# placa_nano.net
KiCad netlist of a schematic drawn in EAGLE
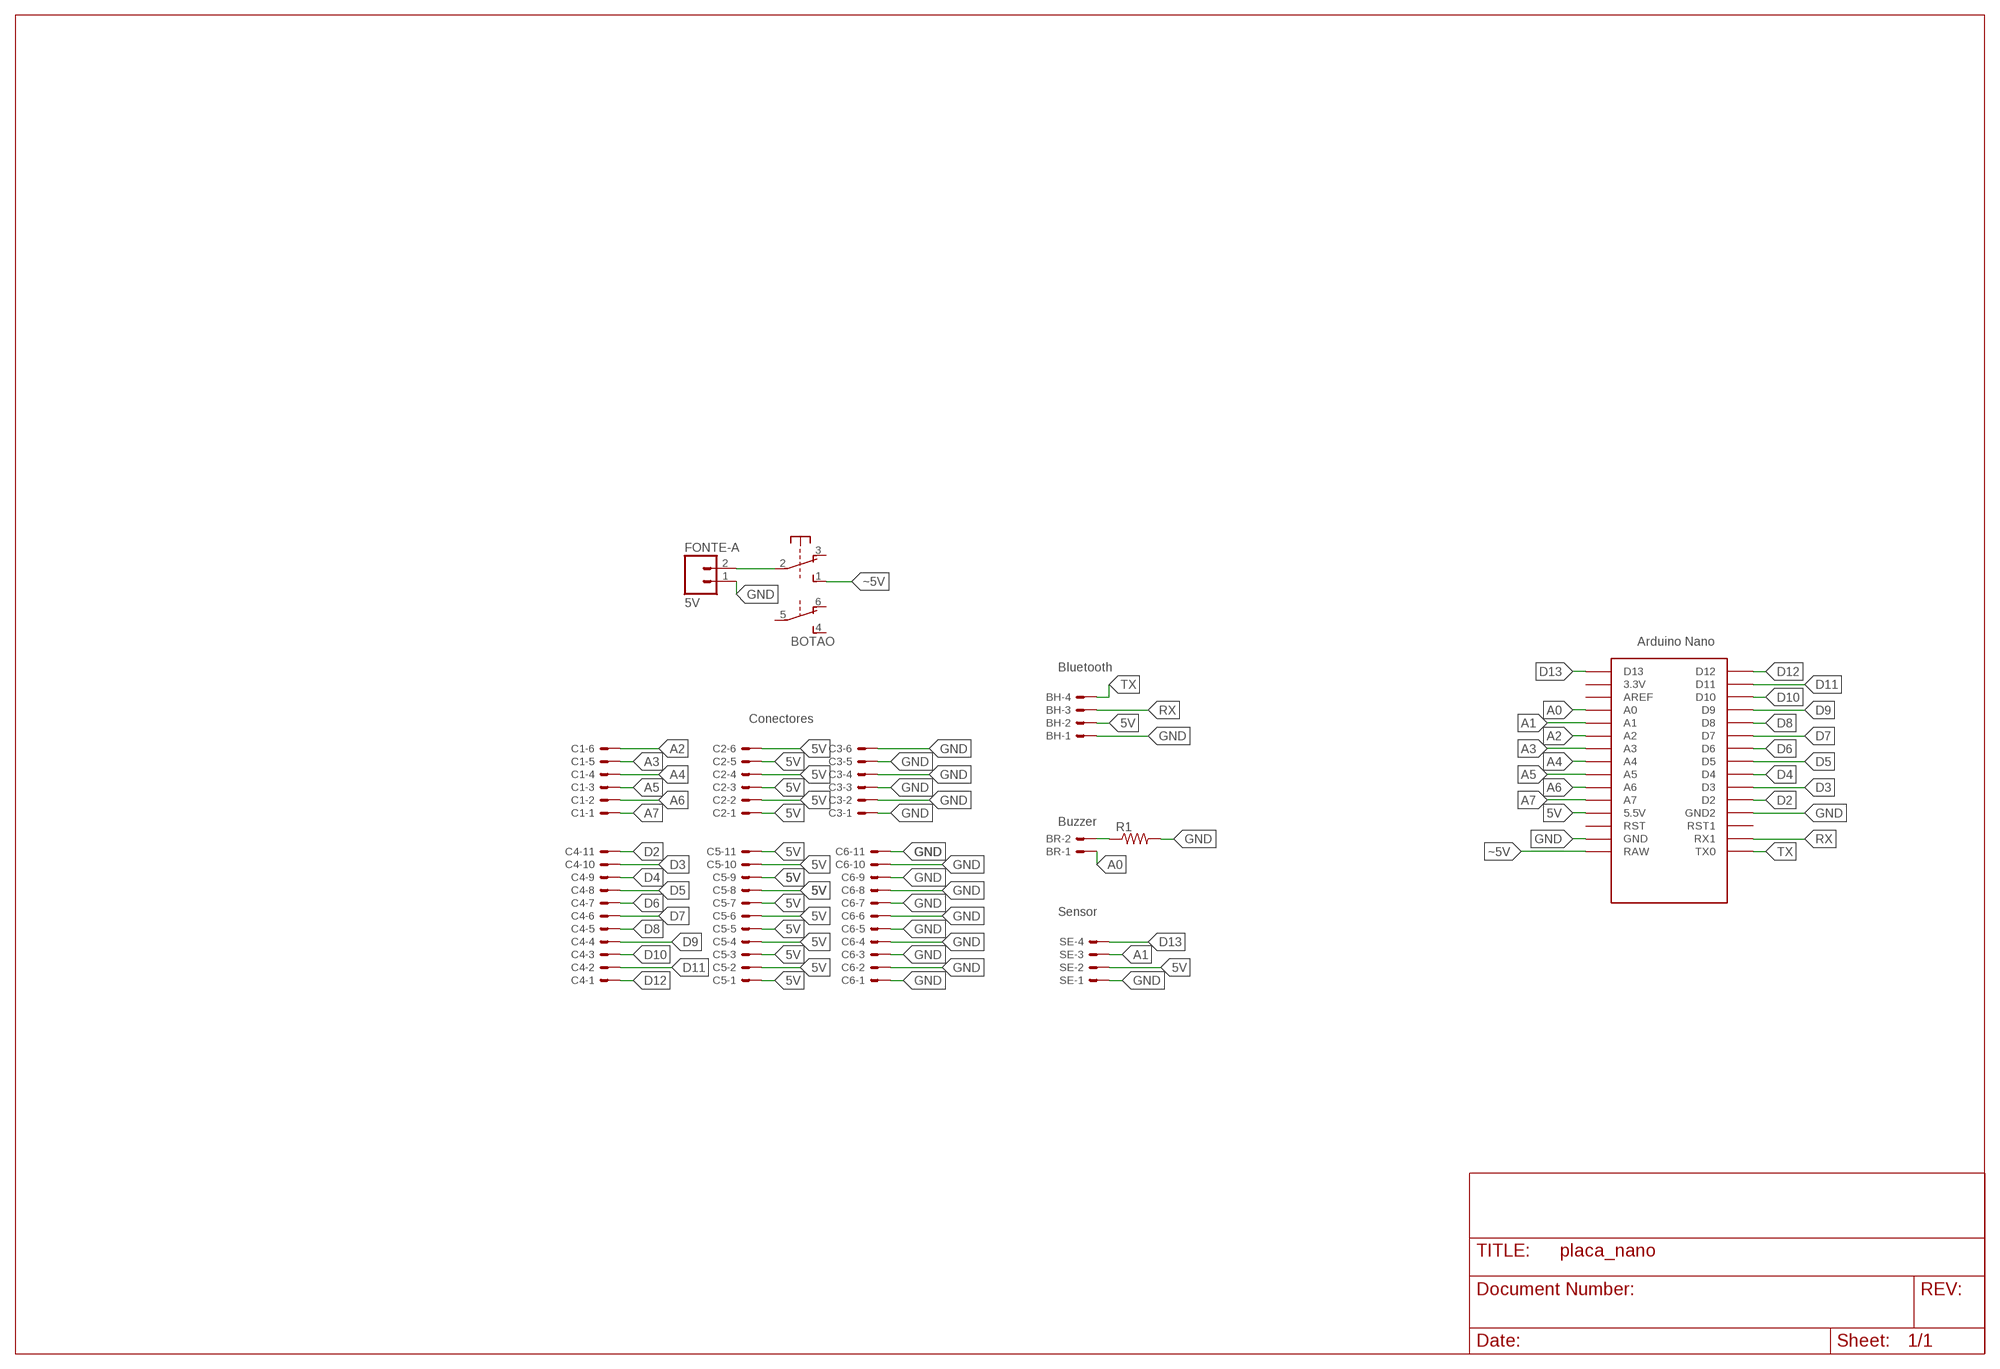
[diagram p0: schematic, sheet 1]

(export (version "E")
  (design (tool "Eeschema 10.0.6"))
  (components
    (comp (ref "BH")
      (value "22-23-2041")
      (footprint "eagle-import:22-23-2041")
      (fields (field (name "MF") "MOLEX"))
      (libsource (lib "eagle-import") (part "22-23-2041"))
    )
    (comp (ref "BOTAO")
      (value "9077-2")
      (footprint "eagle-import:9077-2")
      (libsource (lib "eagle-import") (part "9077-2"))
    )
    (comp (ref "BR")
      (value "22-23-2021")
      (footprint "eagle-import:22-23-2021")
      (fields (field (name "MF") "MOLEX"))
      (libsource (lib "eagle-import") (part "22-23-2021"))
    )
    (comp (ref "C1")
      (value "22-23-2061")
      (footprint "eagle-import:22-23-2061")
      (fields (field (name "MF") "MOLEX"))
      (libsource (lib "eagle-import") (part "22-23-2061"))
    )
    (comp (ref "C2")
      (value "22-23-2061")
      (footprint "eagle-import:22-23-2061")
      (fields (field (name "MF") "MOLEX"))
      (libsource (lib "eagle-import") (part "22-23-2061"))
    )
    (comp (ref "C3")
      (value "22-23-2061")
      (footprint "eagle-import:22-23-2061")
      (fields (field (name "MF") "MOLEX"))
      (libsource (lib "eagle-import") (part "22-23-2061"))
    )
    (comp (ref "C4")
      (value "22-23-2111")
      (footprint "eagle-import:22-23-2111")
      (fields (field (name "MF") "MOLEX"))
      (libsource (lib "eagle-import") (part "22-23-2111"))
    )
    (comp (ref "C5")
      (value "22-23-2111")
      (footprint "eagle-import:22-23-2111")
      (fields (field (name "MF") "MOLEX"))
      (libsource (lib "eagle-import") (part "22-23-2111"))
    )
    (comp (ref "C6")
      (value "22-23-2111")
      (footprint "eagle-import:22-23-2111")
      (fields (field (name "MF") "MOLEX"))
      (libsource (lib "eagle-import") (part "22-23-2111"))
    )
    (comp (ref "FONTE-A")
      (value "5V")
      (footprint "eagle-import:02P")
      (libsource (lib "eagle-import") (part "M02"))
    )
    (comp (ref "R1")
      (value "R-US_0207/10")
      (footprint "eagle-import:0207_10")
      (libsource (lib "eagle-import") (part "R-US_0207/10"))
    )
    (comp (ref "SE")
      (value "22-23-2041")
      (footprint "eagle-import:22-23-2041")
      (fields (field (name "MF") "MOLEX"))
      (libsource (lib "eagle-import") (part "22-23-2041"))
    )
    (comp (ref "U$1")
      (value "NANO")
      (footprint "eagle-import:NANO")
      (libsource (lib "eagle-import") (part "NANO"))
    )
  )
  (nets
    (net (code "1") (name "/~{5V}") (class "Default")
      (node (ref "BOTAO") (pin "1") (pinfunction "S_1") (pintype "passive"))
      (node (ref "BOTAO") (pin "2") (pinfunction "P_2") (pintype "passive"))
      (node (ref "FONTE-A") (pin "2") (pinfunction "2_2") (pintype "passive"))
      (node (ref "U$1") (pin "RAW") (pinfunction "RAW_RAW") (pintype "bidirectional"))
    )
    (net (code "2") (name "5V") (class "Default")
      (node (ref "BH") (pin "2") (pinfunction "S_2") (pintype "passive"))
      (node (ref "C2") (pin "1") (pinfunction "S_1") (pintype "passive"))
      (node (ref "C2") (pin "2") (pinfunction "S_2") (pintype "passive"))
      (node (ref "C2") (pin "3") (pinfunction "S_3") (pintype "passive"))
      (node (ref "C2") (pin "4") (pinfunction "S_4") (pintype "passive"))
      (node (ref "C2") (pin "5") (pinfunction "S_5") (pintype "passive"))
      (node (ref "C2") (pin "6") (pinfunction "S_6") (pintype "passive"))
      (node (ref "C5") (pin "1") (pinfunction "S_1") (pintype "passive"))
      (node (ref "C5") (pin "10") (pinfunction "S_10") (pintype "passive"))
      (node (ref "C5") (pin "11") (pinfunction "S_11") (pintype "passive"))
      (node (ref "C5") (pin "2") (pinfunction "S_2") (pintype "passive"))
      (node (ref "C5") (pin "3") (pinfunction "S_3") (pintype "passive"))
      (node (ref "C5") (pin "4") (pinfunction "S_4") (pintype "passive"))
      (node (ref "C5") (pin "5") (pinfunction "S_5") (pintype "passive"))
      (node (ref "C5") (pin "6") (pinfunction "S_6") (pintype "passive"))
      (node (ref "C5") (pin "7") (pinfunction "S_7") (pintype "passive"))
      (node (ref "C5") (pin "8") (pinfunction "S_8") (pintype "passive"))
      (node (ref "C5") (pin "9") (pinfunction "S_9") (pintype "passive"))
      (node (ref "SE") (pin "2") (pinfunction "S_2") (pintype "passive"))
      (node (ref "U$1") (pin "5V") (pinfunction "5.5V_5V") (pintype "bidirectional"))
    )
    (net (code "3") (name "A0") (class "Default")
      (node (ref "BR") (pin "1") (pinfunction "S_1") (pintype "passive"))
      (node (ref "U$1") (pin "A0") (pinfunction "A0_A0") (pintype "bidirectional"))
    )
    (net (code "4") (name "A1") (class "Default")
      (node (ref "SE") (pin "3") (pinfunction "S_3") (pintype "passive"))
      (node (ref "U$1") (pin "A1") (pinfunction "A1_A1") (pintype "bidirectional"))
    )
    (net (code "5") (name "A2") (class "Default")
      (node (ref "C1") (pin "6") (pinfunction "S_6") (pintype "passive"))
      (node (ref "U$1") (pin "A2") (pinfunction "A2_A2") (pintype "bidirectional"))
    )
    (net (code "6") (name "A3") (class "Default")
      (node (ref "C1") (pin "5") (pinfunction "S_5") (pintype "passive"))
      (node (ref "U$1") (pin "A3") (pinfunction "A3_A3") (pintype "bidirectional"))
    )
    (net (code "7") (name "A4") (class "Default")
      (node (ref "C1") (pin "4") (pinfunction "S_4") (pintype "passive"))
      (node (ref "U$1") (pin "A4") (pinfunction "A4_A4") (pintype "bidirectional"))
    )
    (net (code "8") (name "A5") (class "Default")
      (node (ref "C1") (pin "3") (pinfunction "S_3") (pintype "passive"))
      (node (ref "U$1") (pin "A5") (pinfunction "A5_A5") (pintype "bidirectional"))
    )
    (net (code "9") (name "A6") (class "Default")
      (node (ref "C1") (pin "2") (pinfunction "S_2") (pintype "passive"))
      (node (ref "U$1") (pin "A6") (pinfunction "A6_A6") (pintype "bidirectional"))
    )
    (net (code "10") (name "A7") (class "Default")
      (node (ref "C1") (pin "1") (pinfunction "S_1") (pintype "passive"))
      (node (ref "U$1") (pin "A7") (pinfunction "A7_A7") (pintype "bidirectional"))
    )
    (net (code "11") (name "D2") (class "Default")
      (node (ref "C4") (pin "11") (pinfunction "S_11") (pintype "passive"))
      (node (ref "U$1") (pin "D2") (pinfunction "D2_D2") (pintype "bidirectional"))
    )
    (net (code "12") (name "D3") (class "Default")
      (node (ref "C4") (pin "10") (pinfunction "S_10") (pintype "passive"))
      (node (ref "U$1") (pin "D3") (pinfunction "D3_D3") (pintype "bidirectional"))
    )
    (net (code "13") (name "D4") (class "Default")
      (node (ref "C4") (pin "9") (pinfunction "S_9") (pintype "passive"))
      (node (ref "U$1") (pin "D4") (pinfunction "D4_D4") (pintype "bidirectional"))
    )
    (net (code "14") (name "D5") (class "Default")
      (node (ref "C4") (pin "8") (pinfunction "S_8") (pintype "passive"))
      (node (ref "U$1") (pin "D5") (pinfunction "D5_D5") (pintype "bidirectional"))
    )
    (net (code "15") (name "D6") (class "Default")
      (node (ref "C4") (pin "7") (pinfunction "S_7") (pintype "passive"))
      (node (ref "U$1") (pin "D6") (pinfunction "D6_D6") (pintype "bidirectional"))
    )
    (net (code "16") (name "D7") (class "Default")
      (node (ref "C4") (pin "6") (pinfunction "S_6") (pintype "passive"))
      (node (ref "U$1") (pin "D7") (pinfunction "D7_D7") (pintype "bidirectional"))
    )
    (net (code "17") (name "D8") (class "Default")
      (node (ref "C4") (pin "5") (pinfunction "S_5") (pintype "passive"))
      (node (ref "U$1") (pin "D8") (pinfunction "D8_D8") (pintype "bidirectional"))
    )
    (net (code "18") (name "D9") (class "Default")
      (node (ref "C4") (pin "4") (pinfunction "S_4") (pintype "passive"))
      (node (ref "U$1") (pin "D9") (pinfunction "D9_D9") (pintype "bidirectional"))
    )
    (net (code "19") (name "D10") (class "Default")
      (node (ref "C4") (pin "3") (pinfunction "S_3") (pintype "passive"))
      (node (ref "U$1") (pin "D10") (pinfunction "D10_D10") (pintype "bidirectional"))
    )
    (net (code "20") (name "D11") (class "Default")
      (node (ref "C4") (pin "2") (pinfunction "S_2") (pintype "passive"))
      (node (ref "U$1") (pin "D11") (pinfunction "D11_D11") (pintype "bidirectional"))
    )
    (net (code "21") (name "D12") (class "Default")
      (node (ref "C4") (pin "1") (pinfunction "S_1") (pintype "passive"))
      (node (ref "U$1") (pin "D12") (pinfunction "D12_D12") (pintype "bidirectional"))
    )
    (net (code "22") (name "D13") (class "Default")
      (node (ref "SE") (pin "4") (pinfunction "S_4") (pintype "passive"))
      (node (ref "U$1") (pin "D13") (pinfunction "D13_D13") (pintype "bidirectional"))
    )
    (net (code "23") (name "GND") (class "Default")
      (node (ref "BH") (pin "1") (pinfunction "S_1") (pintype "passive"))
      (node (ref "C3") (pin "1") (pinfunction "S_1") (pintype "passive"))
      (node (ref "C3") (pin "2") (pinfunction "S_2") (pintype "passive"))
      (node (ref "C3") (pin "3") (pinfunction "S_3") (pintype "passive"))
      (node (ref "C3") (pin "4") (pinfunction "S_4") (pintype "passive"))
      (node (ref "C3") (pin "5") (pinfunction "S_5") (pintype "passive"))
      (node (ref "C3") (pin "6") (pinfunction "S_6") (pintype "passive"))
      (node (ref "C6") (pin "1") (pinfunction "S_1") (pintype "passive"))
      (node (ref "C6") (pin "10") (pinfunction "S_10") (pintype "passive"))
      (node (ref "C6") (pin "11") (pinfunction "S_11") (pintype "passive"))
      (node (ref "C6") (pin "2") (pinfunction "S_2") (pintype "passive"))
      (node (ref "C6") (pin "3") (pinfunction "S_3") (pintype "passive"))
      (node (ref "C6") (pin "4") (pinfunction "S_4") (pintype "passive"))
      (node (ref "C6") (pin "5") (pinfunction "S_5") (pintype "passive"))
      (node (ref "C6") (pin "6") (pinfunction "S_6") (pintype "passive"))
      (node (ref "C6") (pin "7") (pinfunction "S_7") (pintype "passive"))
      (node (ref "C6") (pin "8") (pinfunction "S_8") (pintype "passive"))
      (node (ref "C6") (pin "9") (pinfunction "S_9") (pintype "passive"))
      (node (ref "FONTE-A") (pin "1") (pinfunction "1_1") (pintype "passive"))
      (node (ref "R1") (pin "2") (pinfunction "2_2") (pintype "passive"))
      (node (ref "SE") (pin "1") (pinfunction "S_1") (pintype "passive"))
      (node (ref "U$1") (pin "GND") (pinfunction "GND_GND") (pintype "bidirectional"))
      (node (ref "U$1") (pin "GND1") (pinfunction "GND2_GND1") (pintype "bidirectional"))
    )
    (net (code "24") (name "Net-(BRB-S)") (class "Default")
      (node (ref "BR") (pin "2") (pinfunction "S_2") (pintype "passive"))
      (node (ref "R1") (pin "1") (pinfunction "1_1") (pintype "passive"))
    )
    (net (code "25") (name "RX") (class "Default")
      (node (ref "BH") (pin "3") (pinfunction "S_3") (pintype "passive"))
      (node (ref "U$1") (pin "RX1") (pinfunction "RX1_RX1") (pintype "bidirectional"))
    )
    (net (code "26") (name "TX") (class "Default")
      (node (ref "BH") (pin "4") (pinfunction "S_4") (pintype "passive"))
      (node (ref "U$1") (pin "TX0") (pinfunction "TX0_TX0") (pintype "bidirectional"))
    )
    (net (code "27") (name "unconnected-(BOTAOA-O-Pad3)") (class "Default")
      (node (ref "BOTAO") (pin "3") (pinfunction "O_3") (pintype "passive"))
    )
    (net (code "28") (name "unconnected-(BOTAOB-O-Pad6)") (class "Default")
      (node (ref "BOTAO") (pin "6") (pinfunction "O_6") (pintype "passive"))
    )
    (net (code "29") (name "unconnected-(BOTAOB-P-Pad5)") (class "Default")
      (node (ref "BOTAO") (pin "5") (pinfunction "P_5") (pintype "passive"))
    )
    (net (code "30") (name "unconnected-(BOTAOB-S-Pad4)") (class "Default")
      (node (ref "BOTAO") (pin "4") (pinfunction "S_4") (pintype "passive"))
    )
    (net (code "31") (name "unconnected-(U$1-Pad3.3V)") (class "Default")
      (node (ref "U$1") (pin "3.3V") (pinfunction "3.3V_3.3V") (pintype "bidirectional"))
    )
    (net (code "32") (name "unconnected-(U$1-PadAREF)") (class "Default")
      (node (ref "U$1") (pin "AREF") (pinfunction "AREF_AREF") (pintype "bidirectional"))
    )
    (net (code "33") (name "unconnected-(U$1-PadRST)") (class "Default")
      (node (ref "U$1") (pin "RST") (pinfunction "RST_RST") (pintype "bidirectional"))
    )
    (net (code "34") (name "unconnected-(U$1-PadRST1)") (class "Default")
      (node (ref "U$1") (pin "RST1") (pinfunction "RST1_RST1") (pintype "bidirectional"))
    )
  )
)
